# IsoDcDc-BSR033A.net
KiCad netlist of a schematic drawn in Altium Designer
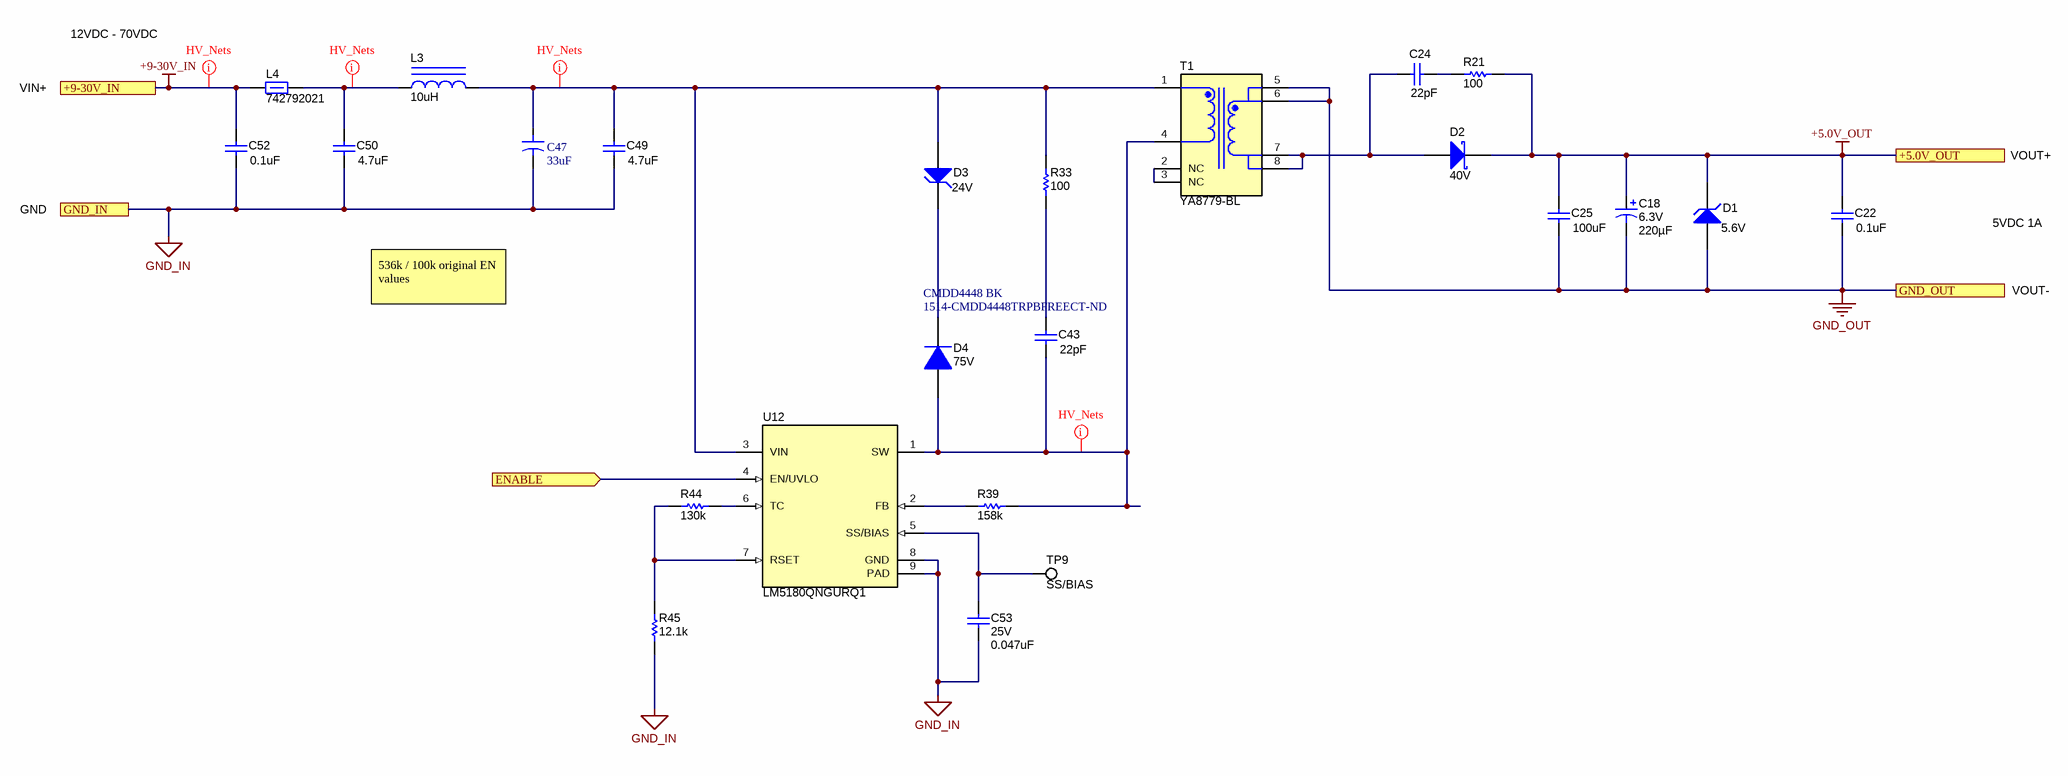
[diagram p0: IsoDcDc-BSR033A.SchDoc]

(export (version "E")
  (design (tool "Eeschema 10.0.6"))
  (components
    (comp (ref "C18")
      (value "T598D107M010ATE025")
      (footprint "7343-31")
      (description "CAP, Aluminum Polymer, 220 µF, 6.3 V,+/- 20%, 0.01 ohm, 7343-31 SMD")
      (fields
        (field (name "MANUFACTURER") "MuRata")
        (field (name "PARTNUMBER") "ECASD60J227M010K00")
        (field (name "VDC_V") "6.3V")
        (field (name "VALUEDISPLAYED") "220µF")
      )
      (libsource (lib "BSR033A") (part "Cap_Polarized"))
    )
    (comp (ref "C22")
      (value "GRM188R72A104KA35J")
      (footprint "0603C")
      (description "CAP, CERM, 0.1 uF, 100 V, +/- 10%, X7R, 0603")
      (fields
        (field (name "MANUFACTURER") "MuRata")
        (field (name "VALUEDISPLAYED") "0.1uF")
        (field (name "PUBLISHER") "Texas Instruments")
      )
      (libsource (lib "BSR033A") (part "CMP-0007470-5"))
    )
    (comp (ref "C24")
      (value "GRM1885C2A220JA01D")
      (footprint "0603C")
      (description "CAP, CERM, 22 pF, 100 V, +/- 5%, C0G/NP0, 0603")
      (fields
        (field (name "MANUFACTURER") "MuRata")
        (field (name "VALUEDISPLAYED") "22pF")
        (field (name "PUBLISHER") "Texas Instruments")
      )
      (libsource (lib "BSR033A") (part "CMP-0007255-4"))
    )
    (comp (ref "C25")
      (value "GRM32EC80J107ME20L")
      (footprint "1210C")
      (description "CAP, CERM, 100 uF, 6.3 V, +/- 20%, X6S, 1210")
      (fields
        (field (name "MANUFACTURER") "MuRata")
        (field (name "VALUEDISPLAYED") "100uF")
        (field (name "PUBLISHER") "Texas Instruments")
      )
      (libsource (lib "BSR033A") (part "Capacitor"))
    )
    (comp (ref "C43")
      (value "GRM1885C2A220JA01D")
      (footprint "0603C")
      (description "CAP, CERM, 22 pF, 100 V, +/- 5%, C0G/NP0, 0603")
      (fields
        (field (name "MANUFACTURER") "MuRata")
        (field (name "VALUEDISPLAYED") "22pF")
        (field (name "PUBLISHER") "Texas Instruments")
      )
      (libsource (lib "BSR033A") (part "CMP-0007255-4"))
    )
    (comp (ref "C47")
      (value "33uF")
      (footprint "CAPC7343X430M")
      (description "33µF Molded Tantalum Polymer Capacitor 50V 2917 (7343 Metric) 75mOhm @ 100kHz")
      (fields (field (name "Comment") "CAP TANTALUM 33UF 50V 2917"))
      (libsource (lib "master-010106") (part "T521X336M050ATE075"))
    )
    (comp (ref "C49")
      (value "GRM32DC72A475KE01L")
      (footprint "1210C")
      (description "CAP, CERM, 4.7 uF, 100 V, +/- 10%, X7S, 1210")
      (fields
        (field (name "MANUFACTURER") "MuRata")
        (field (name "VALUEDISPLAYED") "4.7uF")
        (field (name "PUBLISHER") "Texas Instruments")
      )
      (libsource (lib "BSR033A") (part "CMP-0009182-2"))
    )
    (comp (ref "C50")
      (value "GRM32DC72A475KE01L")
      (footprint "1210C")
      (description "CAP, CERM, 4.7 uF, 100 V, +/- 10%, X7S, 1210")
      (fields
        (field (name "MANUFACTURER") "MuRata")
        (field (name "VALUEDISPLAYED") "4.7uF")
        (field (name "PUBLISHER") "Texas Instruments")
      )
      (libsource (lib "BSR033A") (part "CMP-0009182-2"))
    )
    (comp (ref "C52")
      (value "GRM188R72A104KA35J")
      (footprint "0603C")
      (description "CAP, CERM, 0.1 uF, 100 V, +/- 10%, X7R, 0603")
      (fields
        (field (name "MANUFACTURER") "MuRata")
        (field (name "VALUEDISPLAYED") "0.1uF")
        (field (name "PUBLISHER") "Texas Instruments")
      )
      (libsource (lib "BSR033A") (part "CMP-0007470-5"))
    )
    (comp (ref "C53")
      (value "GCM188R71E473KA37D")
      (footprint "0603C")
      (description "CAP, CERM, 0.047 uF, 25 V, +/- 10%, X7R, AEC-Q200 Grade 1, 0603")
      (fields
        (field (name "MANUFACTURER") "MuRata")
        (field (name "VDC_V") "25V")
        (field (name "VALUEDISPLAYED") "0.047uF")
        (field (name "PUBLISHER") "Texas Instruments")
      )
      (libsource (lib "BSR033A") (part "CMP-0007141-5"))
    )
    (comp (ref "D1")
      (value "MMSZ5232BS-7-F")
      (footprint "SOD-323")
      (description "Diode, Zener, 5.6 V, 200 mW, SOD-323")
      (fields
        (field (name "VZ_V") "5.6V")
        (field (name "MANUFACTURER") "Diodes Inc.")
        (field (name "PUBLISHER") "Texas Instruments")
      )
      (libsource (lib "BSR033A") (part "CMP-0005855-1"))
    )
    (comp (ref "D2")
      (value "40V")
      (footprint "SMAF")
      (description "Diode, Schottky, 40 V, 3 A, AEC-Q101, SMAF")
      (fields
        (field (name "PARTNUMBER") "FSV340AF")
        (field (name "MANUFACTURER") "Fairchild Semiconductor")
        (field (name "PUBLISHER") "Texas Instruments")
      )
      (libsource (lib "BSR033A") (part "CMP-0028855-1"))
    )
    (comp (ref "D3")
      (value "DFLZ24-7")
      (footprint "PowerDI123")
      (description "Diode, Zener, 24 V, 1 W, PowerDI123")
      (fields
        (field (name "VZ_V") "24V")
        (field (name "MANUFACTURER") "Diodes Inc.")
        (field (name "PUBLISHER") "Texas Instruments")
      )
      (libsource (lib "BSR033A") (part "CMP-0005415-2"))
    )
    (comp (ref "D4")
      (value "75V")
      (footprint "SOD-323")
      (description "Diode, Ultrafast, 75 V, 0.25 A, SOD-323")
      (fields
        (field (name "MANUFACTURER") "Central Semiconductor")
        (field (name "PARTNUMBER") "CMDD4448")
        (field (name "SUPPLIER PART NUMBER 1") "1514-CMDD4448TRPBFREECT-ND")
        (field (name "SUPPLIER PART NUMBER 2") "CMDD4448 BK")
        (field (name "PUBLISHER") "Texas Instruments")
      )
      (libsource (lib "BSR033A") (part "CMP-0029019-1"))
    )
    (comp (ref "L3")
      (value "744042100")
      (footprint "WE-TPC-M1")
      (description "Inductor, Shielded Drum Core, Ferrite, 10 uH, 1 A, 0.12 ohm, SMD")
      (fields
        (field (name "MANUFACTURER") "Wurth Elektronik")
        (field (name "VALUEDISPLAYED") "10uH")
        (field (name "PUBLISHER") "Texas Instruments")
      )
      (libsource (lib "BSR033A") (part "CMP-0063804-1"))
    )
    (comp (ref "L4")
      (value "742792021")
      (footprint "0805_HV")
      (description "Ferrite Bead, 22 ohm @ 100 MHz, 6 A, 0805")
      (fields (field (name "MANUFACTURER") "Wurth Elektronik") (field (name "PUBLISHER") "Texas Instruments"))
      (libsource (lib "BSR033A") (part "Ferrite_Bead"))
    )
    (comp (ref "R21")
      (value "CRCW0603100RFKEA")
      (footprint "0603R")
      (description "RES, 100, 1%, 0.1 W, 0603")
      (fields
        (field (name "MANUFACTURER") "Vishay-Dale")
        (field (name "VALUEDISPLAYED") "100")
        (field (name "PUBLISHER") "Texas Instruments")
      )
      (libsource (lib "BSR033A") (part "CMP-0021991-3"))
    )
    (comp (ref "R33")
      (value "CRCW0603100RFKEA")
      (footprint "0603R")
      (description "RES, 100, 1%, 0.1 W, 0603")
      (fields
        (field (name "MANUFACTURER") "Vishay-Dale")
        (field (name "VALUEDISPLAYED") "100")
        (field (name "PUBLISHER") "Texas Instruments")
      )
      (libsource (lib "BSR033A") (part "CMP-0021991-3"))
    )
    (comp (ref "R39")
      (value "CRCW0603158KFKEA")
      (footprint "0603R")
      (description "RES, 158 k, 1%, 0.1 W, AEC-Q200 Grade 0, 0603")
      (fields (field (name "MANUFACTURER") "Vishay-Dale") (field (name "VALUEDISPLAYED") "158k"))
      (libsource (lib "BSR033A") (part "CMP-0022064-4"))
    )
    (comp (ref "R44")
      (value "CRCW0603130KFKEA")
      (footprint "0603R")
      (description "RES, 130 k, 1%, 0.1 W, AEC-Q200 Grade 0, 0603")
      (fields (field (name "MANUFACTURER") "Vishay-Dale") (field (name "VALUEDISPLAYED") "130k"))
      (libsource (lib "BSR033A") (part "CMP-0022036-4"))
    )
    (comp (ref "R45")
      (value "CRCW060312K1FKEA")
      (footprint "0603R")
      (description "RES, 12.1 k, 1%, 0.1 W, 0603")
      (fields
        (field (name "MANUFACTURER") "Vishay-Dale")
        (field (name "VALUEDISPLAYED") "12.1k")
        (field (name "PUBLISHER") "Texas Instruments")
      )
      (libsource (lib "BSR033A") (part "CMP-0022030-3"))
    )
    (comp (ref "T1")
      (value "YA8779-BL")
      (footprint "Coilcraft_YA8779-CL")
      (description "Transformer, 30 uH, SMD")
      (fields (field (name "MANUFACTURER") "Coilcraft"))
      (libsource (lib "BSR033A") (part "Coilcraft_YA8779-CL"))
    )
    (comp (ref "TP9")
      (value "SS/BIAS")
      (footprint "Testpoint_Keystone_Miniature")
      (description "Test Point, Miniature, SMT")
      (fields
        (field (name "MANUFACTURER") "Keystone")
        (field (name "PARTNUMBER") "5015")
        (field (name "PUBLISHER") "Texas Instruments")
      )
      (libsource (lib "BSR033A") (part "CMP-0055152-1"))
    )
    (comp (ref "U12")
      (value "LM5180QNGURQ1")
      (footprint "NGU0008C")
      (description "70-V PSR Flyback Converter With 100-V, 1.2-A Power Switch and Ultra-Low IQ, NGU0008C (WSON-8)")
      (fields
        (field (name "ALTERNATE PARTNUMBER") "LM5180QNGUTQ1")
        (field (name "MANUFACTURER") "Texas Instruments")
        (field (name "PARTNUMBER") "LM5180QNGURQ1")
      )
      (libsource (lib "BSR033A") (part "LM5180-Q1"))
    )
  )
  (nets
    (net (code "1") (name "+5.0V_OUT") (class "Default")
      (node (ref "C18") (pin "1") (pinfunction "+_1") (pintype "passive"))
      (node (ref "C22") (pin "1") (pinfunction "1_1") (pintype "passive"))
      (node (ref "C25") (pin "1") (pinfunction "1_1") (pintype "passive"))
      (node (ref "D1") (pin "1") (pinfunction "K_1") (pintype "passive"))
      (node (ref "D2") (pin "1") (pinfunction "K_1") (pintype "passive"))
      (node (ref "R21") (pin "1") (pinfunction "1_1") (pintype "passive"))
    )
    (net (code "2") (name "+9-30V_IN") (class "Default")
      (node (ref "C52") (pin "1") (pinfunction "1_1") (pintype "passive"))
      (node (ref "L4") (pin "1") (pinfunction "1_1") (pintype "passive"))
    )
    (net (code "3") (name "/ENABLE") (class "Default")
      (node (ref "U12") (pin "4") (pinfunction "EN/UVLO_4") (pintype "input"))
    )
    (net (code "4") (name "GND_IN") (class "Default")
      (node (ref "C47") (pin "2") (pinfunction "2_2") (pintype "passive"))
      (node (ref "C49") (pin "1") (pinfunction "1_1") (pintype "passive"))
      (node (ref "C50") (pin "1") (pinfunction "1_1") (pintype "passive"))
      (node (ref "C52") (pin "2") (pinfunction "2_2") (pintype "passive"))
      (node (ref "C53") (pin "2") (pinfunction "2_2") (pintype "passive"))
      (node (ref "R45") (pin "1") (pinfunction "1_1") (pintype "passive"))
      (node (ref "U12") (pin "8") (pinfunction "GND_8") (pintype "power_in"))
      (node (ref "U12") (pin "9") (pinfunction "PAD_9") (pintype "power_in"))
    )
    (net (code "5") (name "GND_OUT") (class "Default")
      (node (ref "C18") (pin "2") (pinfunction "-_2") (pintype "passive"))
      (node (ref "C22") (pin "2") (pinfunction "2_2") (pintype "passive"))
      (node (ref "C25") (pin "2") (pinfunction "2_2") (pintype "passive"))
      (node (ref "D1") (pin "2") (pinfunction "A_2") (pintype "passive"))
      (node (ref "T1") (pin "5") (pinfunction "5_5") (pintype "passive"))
      (node (ref "T1") (pin "6") (pinfunction "6_6") (pintype "passive"))
    )
    (net (code "6") (name "Net-(C24-Pad1)") (class "Default")
      (node (ref "C24") (pin "1") (pinfunction "1_1") (pintype "passive"))
      (node (ref "R21") (pin "2") (pinfunction "2_2") (pintype "passive"))
    )
    (net (code "7") (name "Net-(C43-Pad1)") (class "Default")
      (node (ref "C43") (pin "1") (pinfunction "1_1") (pintype "passive"))
      (node (ref "R33") (pin "1") (pinfunction "1_1") (pintype "passive"))
    )
    (net (code "8") (name "Net-(C50-Pad2)") (class "Default")
      (node (ref "C50") (pin "2") (pinfunction "2_2") (pintype "passive"))
      (node (ref "L3") (pin "1") (pinfunction "1_1") (pintype "passive"))
      (node (ref "L4") (pin "2") (pinfunction "2_2") (pintype "passive"))
    )
    (net (code "9") (name "Net-(D2-A)") (class "Default")
      (node (ref "C24") (pin "2") (pinfunction "2_2") (pintype "passive"))
      (node (ref "D2") (pin "2") (pinfunction "A_2") (pintype "passive"))
      (node (ref "T1") (pin "7") (pinfunction "7_7") (pintype "passive"))
      (node (ref "T1") (pin "8") (pinfunction "8_8") (pintype "passive"))
    )
    (net (code "10") (name "Net-(D3-A)") (class "Default")
      (node (ref "C47") (pin "1") (pinfunction "1_1") (pintype "passive"))
      (node (ref "C49") (pin "2") (pinfunction "2_2") (pintype "passive"))
      (node (ref "D3") (pin "2") (pinfunction "A_2") (pintype "passive"))
      (node (ref "L3") (pin "2") (pinfunction "2_2") (pintype "passive"))
      (node (ref "R33") (pin "2") (pinfunction "2_2") (pintype "passive"))
      (node (ref "T1") (pin "1") (pinfunction "1_1") (pintype "passive"))
      (node (ref "U12") (pin "3") (pinfunction "VIN_3") (pintype "power_in"))
    )
    (net (code "11") (name "Net-(D3-K)") (class "Default")
      (node (ref "D3") (pin "1") (pinfunction "K_1") (pintype "passive"))
      (node (ref "D4") (pin "1") (pinfunction "K_1") (pintype "passive"))
    )
    (net (code "12") (name "Net-(D4-A)") (class "Default")
      (node (ref "C43") (pin "2") (pinfunction "2_2") (pintype "passive"))
      (node (ref "D4") (pin "2") (pinfunction "A_2") (pintype "passive"))
      (node (ref "R39") (pin "2") (pinfunction "2_2") (pintype "passive"))
      (node (ref "T1") (pin "4") (pinfunction "4_4") (pintype "passive"))
      (node (ref "U12") (pin "1") (pinfunction "SW_1") (pintype "power_in"))
    )
    (net (code "13") (name "Net-(T1-NC-Pad2)") (class "Default")
      (node (ref "T1") (pin "2") (pinfunction "NC_2") (pintype "passive"))
      (node (ref "T1") (pin "3") (pinfunction "NC_3") (pintype "passive"))
    )
    (net (code "14") (name "Net-(U12-FB)") (class "Default")
      (node (ref "R39") (pin "1") (pinfunction "1_1") (pintype "passive"))
      (node (ref "U12") (pin "2") (pinfunction "FB_2") (pintype "input"))
    )
    (net (code "15") (name "Net-(U12-RSET)") (class "Default")
      (node (ref "R44") (pin "1") (pinfunction "1_1") (pintype "passive"))
      (node (ref "R45") (pin "2") (pinfunction "2_2") (pintype "passive"))
      (node (ref "U12") (pin "7") (pinfunction "RSET_7") (pintype "input"))
    )
    (net (code "16") (name "Net-(U12-SS{slash}BIAS)") (class "Default")
      (node (ref "C53") (pin "1") (pinfunction "1_1") (pintype "passive"))
      (node (ref "TP9") (pin "1") (pintype "passive"))
      (node (ref "U12") (pin "5") (pinfunction "SS/BIAS_5") (pintype "input"))
    )
    (net (code "17") (name "Net-(U12-TC)") (class "Default")
      (node (ref "R44") (pin "2") (pinfunction "2_2") (pintype "passive"))
      (node (ref "U12") (pin "6") (pinfunction "TC_6") (pintype "input"))
    )
  )
)
